# 150HzLPF_8GainPreamp.net
KiCad netlist of a schematic drawn in EAGLE
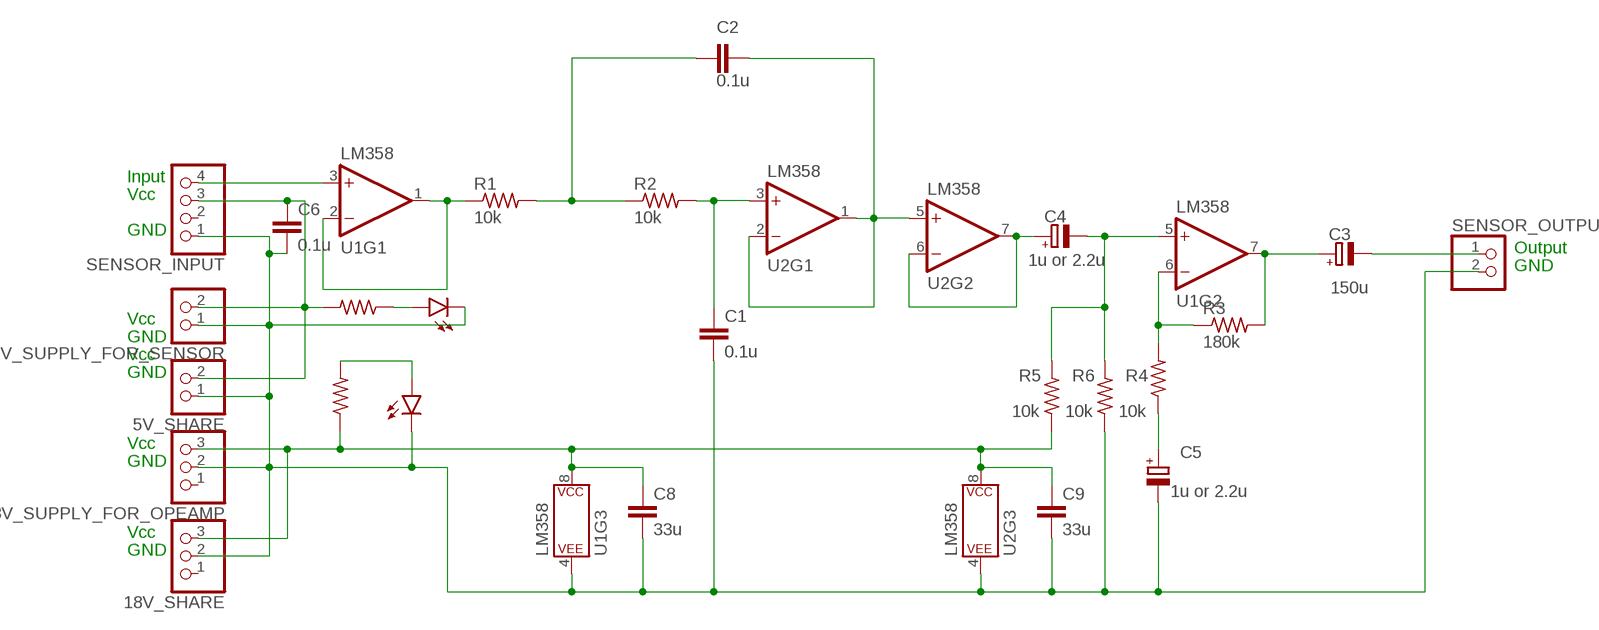
[diagram p0: schematic, sheet 1]

(export (version "E")
  (design (tool "Eeschema 10.0.6"))
  (components
    (comp (ref "5V_SHARE")
      (value "PINHD-1X2")
      (footprint "eagle-import:1X02")
      (libsource (lib "eagle-import") (part "PINHD-1X2"))
    )
    (comp (ref "5V_SUPPLY_FOR_SENSOR")
      (value "PINHD-1X2")
      (footprint "eagle-import:1X02")
      (libsource (lib "eagle-import") (part "PINHD-1X2"))
    )
    (comp (ref "18V_SHARE")
      (value "PINHD-1X3")
      (footprint "eagle-import:1X03")
      (libsource (lib "eagle-import") (part "PINHD-1X3"))
    )
    (comp (ref "18V_SUPPLY_FOR_OPEAMP")
      (value "PINHD-1X3")
      (footprint "eagle-import:1X03")
      (libsource (lib "eagle-import") (part "PINHD-1X3"))
    )
    (comp (ref "C1")
      (value "0.1u")
      (footprint "eagle-import:C050-030X075")
      (libsource (lib "eagle-import") (part "C-EU050-030X075"))
    )
    (comp (ref "C2")
      (value "0.1u")
      (footprint "eagle-import:C050-030X075")
      (libsource (lib "eagle-import") (part "C-EU050-030X075"))
    )
    (comp (ref "C3")
      (value "150u")
      (footprint "eagle-import:E5-10,5")
      (libsource (lib "eagle-import") (part "CPOL-EUE5-10.5"))
    )
    (comp (ref "C4")
      (value "1u or 2.2u")
      (footprint "eagle-import:E5-10,5")
      (libsource (lib "eagle-import") (part "CPOL-EUE5-10.5"))
    )
    (comp (ref "C5")
      (value "1u or 2.2u")
      (footprint "eagle-import:E5-10,5")
      (libsource (lib "eagle-import") (part "CPOL-EUE5-10.5"))
    )
    (comp (ref "C6")
      (value "0.1u")
      (footprint "eagle-import:C0603")
      (libsource (lib "eagle-import") (part "C-EUC0603"))
    )
    (comp (ref "C8")
      (value "33u")
      (footprint "eagle-import:C0603")
      (libsource (lib "eagle-import") (part "C-EUC0603"))
    )
    (comp (ref "C9")
      (value "33u")
      (footprint "eagle-import:C0603")
      (libsource (lib "eagle-import") (part "C-EUC0603"))
    )
    (comp (ref "D2")
      (value "LTL-1CHE")
      (footprint "eagle-import:RADIAL_3MM")
      (fields
        (field (name "DIGIKEY_PART_NUMBER") "160-1708-ND")
        (field (name "MANUFACTURER") "Lite-On Inc.")
        (field (name "CREATED_BY") "PCBLayout.com")
      )
      (libsource (lib "eagle-import") (part "LTL-1CHE"))
    )
    (comp (ref "D3")
      (value "LTL-1CHE")
      (footprint "eagle-import:RADIAL_3MM")
      (fields
        (field (name "DIGIKEY_PART_NUMBER") "160-1708-ND")
        (field (name "MANUFACTURER") "Lite-On Inc.")
        (field (name "CREATED_BY") "PCBLayout.com")
      )
      (libsource (lib "eagle-import") (part "LTL-1CHE"))
    )
    (comp (ref "R1")
      (value "10k")
      (footprint "eagle-import:0207_7")
      (libsource (lib "eagle-import") (part "R-US_0207/7"))
    )
    (comp (ref "R2")
      (value "10k")
      (footprint "eagle-import:0207_7")
      (libsource (lib "eagle-import") (part "R-US_0207/7"))
    )
    (comp (ref "R3")
      (value "180k")
      (footprint "eagle-import:0207_7")
      (libsource (lib "eagle-import") (part "R-US_0207/7"))
    )
    (comp (ref "R4")
      (value "10k")
      (footprint "eagle-import:0207_7")
      (libsource (lib "eagle-import") (part "R-US_0207/7"))
    )
    (comp (ref "R5")
      (value "10k")
      (footprint "eagle-import:0207_7")
      (libsource (lib "eagle-import") (part "R-US_0207/7"))
    )
    (comp (ref "R6")
      (value "10k")
      (footprint "eagle-import:0207_7")
      (libsource (lib "eagle-import") (part "R-US_0207/7"))
    )
    (comp (ref "R8")
      (value "760")
      (footprint "eagle-import:0207_7")
      (libsource (lib "eagle-import") (part "R-US_0207/7"))
    )
    (comp (ref "R9")
      (value "3.3k")
      (footprint "eagle-import:0207_7")
      (libsource (lib "eagle-import") (part "R-US_0207/7"))
    )
    (comp (ref "SENSOR_INPUT")
      (value "PINHD-1X4")
      (footprint "eagle-import:1X04")
      (libsource (lib "eagle-import") (part "PINHD-1X4"))
    )
    (comp (ref "SENSOR_OUTPUT")
      (value "PINHD-1X2")
      (footprint "eagle-import:1X02")
      (libsource (lib "eagle-import") (part "PINHD-1X2"))
    )
    (comp (ref "U1")
      (value "LM358")
      (footprint "eagle-import:DIP08")
      (libsource (lib "eagle-import") (part "LM358"))
    )
    (comp (ref "U2")
      (value "LM358")
      (footprint "eagle-import:DIP08")
      (libsource (lib "eagle-import") (part "LM358"))
    )
  )
  (nets
    (net (code "1") (name "Net-(5V_SHARE-Pad2)") (class "Default")
      (node (ref "5V_SHARE") (pin "2") (pinfunction "2_2") (pintype "passive"))
      (node (ref "5V_SUPPLY_FOR_SENSOR") (pin "2") (pinfunction "2_2") (pintype "passive"))
      (node (ref "C6") (pin "1") (pinfunction "1_1") (pintype "passive"))
      (node (ref "R8") (pin "2") (pinfunction "2_2") (pintype "passive"))
      (node (ref "SENSOR_INPUT") (pin "3") (pinfunction "3_3") (pintype "passive"))
    )
    (net (code "2") (name "Net-(C2-Pad2)") (class "Default")
      (node (ref "C2") (pin "2") (pinfunction "2_2") (pintype "passive"))
      (node (ref "R1") (pin "2") (pinfunction "2_2") (pintype "passive"))
      (node (ref "R2") (pin "1") (pinfunction "1_1") (pintype "passive"))
    )
    (net (code "3") (name "Net-(C3-Pad-)") (class "Default")
      (node (ref "C3") (pin "-") (pinfunction "-_-") (pintype "passive"))
      (node (ref "SENSOR_OUTPUT") (pin "1") (pinfunction "1_1") (pintype "passive"))
    )
    (net (code "4") (name "Net-(C5-Pad+)") (class "Default")
      (node (ref "C5") (pin "+") (pinfunction "+_+") (pintype "passive"))
      (node (ref "R4") (pin "1") (pinfunction "1_1") (pintype "passive"))
    )
    (net (code "5") (name "Net-(D2-PadA)") (class "Default")
      (node (ref "D2") (pin "A") (pinfunction "A_A") (pintype "passive"))
      (node (ref "R8") (pin "1") (pinfunction "1_1") (pintype "passive"))
    )
    (net (code "6") (name "Net-(D3-PadA)") (class "Default")
      (node (ref "D3") (pin "A") (pinfunction "A_A") (pintype "passive"))
      (node (ref "R9") (pin "2") (pinfunction "2_2") (pintype "passive"))
    )
    (net (code "7") (name "Net-(U1A-+IN)") (class "Default")
      (node (ref "SENSOR_INPUT") (pin "4") (pinfunction "4_4") (pintype "passive"))
      (node (ref "U1") (pin "3") (pinfunction "+IN_3") (pintype "input"))
    )
    (net (code "8") (name "Net-(U1A--IN)") (class "Default")
      (node (ref "R1") (pin "1") (pinfunction "1_1") (pintype "passive"))
      (node (ref "U1") (pin "1") (pinfunction "OUT_1") (pintype "output"))
      (node (ref "U1") (pin "2") (pinfunction "-IN_2") (pintype "input"))
    )
    (net (code "9") (name "Net-(U1B-+IN)") (class "Default")
      (node (ref "C4") (pin "-") (pinfunction "-_-") (pintype "passive"))
      (node (ref "R5") (pin "2") (pinfunction "2_2") (pintype "passive"))
      (node (ref "R6") (pin "2") (pinfunction "2_2") (pintype "passive"))
      (node (ref "U1") (pin "5") (pinfunction "+IN_5") (pintype "input"))
    )
    (net (code "10") (name "Net-(U1B--IN)") (class "Default")
      (node (ref "R3") (pin "1") (pinfunction "1_1") (pintype "passive"))
      (node (ref "R4") (pin "2") (pinfunction "2_2") (pintype "passive"))
      (node (ref "U1") (pin "6") (pinfunction "-IN_6") (pintype "input"))
    )
    (net (code "11") (name "Net-(U1B-OUT)") (class "Default")
      (node (ref "C3") (pin "+") (pinfunction "+_+") (pintype "passive"))
      (node (ref "R3") (pin "2") (pinfunction "2_2") (pintype "passive"))
      (node (ref "U1") (pin "7") (pinfunction "OUT_7") (pintype "output"))
    )
    (net (code "12") (name "Net-(U1C-P$V+)") (class "Default")
      (node (ref "18V_SHARE") (pin "3") (pinfunction "3_3") (pintype "passive"))
      (node (ref "18V_SUPPLY_FOR_OPEAMP") (pin "3") (pinfunction "3_3") (pintype "passive"))
      (node (ref "C8") (pin "1") (pinfunction "1_1") (pintype "passive"))
      (node (ref "C9") (pin "1") (pinfunction "1_1") (pintype "passive"))
      (node (ref "R5") (pin "1") (pinfunction "1_1") (pintype "passive"))
      (node (ref "R9") (pin "1") (pinfunction "1_1") (pintype "passive"))
      (node (ref "U1") (pin "8") (pinfunction "P$V+_8") (pintype "bidirectional"))
      (node (ref "U2") (pin "8") (pinfunction "P$V+_8") (pintype "bidirectional"))
    )
    (net (code "13") (name "Net-(U1C-P$V-)") (class "Default")
      (node (ref "18V_SHARE") (pin "2") (pinfunction "2_2") (pintype "passive"))
      (node (ref "18V_SUPPLY_FOR_OPEAMP") (pin "2") (pinfunction "2_2") (pintype "passive"))
      (node (ref "5V_SHARE") (pin "1") (pinfunction "1_1") (pintype "passive"))
      (node (ref "5V_SUPPLY_FOR_SENSOR") (pin "1") (pinfunction "1_1") (pintype "passive"))
      (node (ref "C1") (pin "2") (pinfunction "2_2") (pintype "passive"))
      (node (ref "C5") (pin "-") (pinfunction "-_-") (pintype "passive"))
      (node (ref "C6") (pin "2") (pinfunction "2_2") (pintype "passive"))
      (node (ref "C8") (pin "2") (pinfunction "2_2") (pintype "passive"))
      (node (ref "C9") (pin "2") (pinfunction "2_2") (pintype "passive"))
      (node (ref "D2") (pin "C") (pinfunction "C_C") (pintype "passive"))
      (node (ref "D3") (pin "C") (pinfunction "C_C") (pintype "passive"))
      (node (ref "R6") (pin "1") (pinfunction "1_1") (pintype "passive"))
      (node (ref "SENSOR_INPUT") (pin "1") (pinfunction "1_1") (pintype "passive"))
      (node (ref "SENSOR_OUTPUT") (pin "2") (pinfunction "2_2") (pintype "passive"))
      (node (ref "U1") (pin "4") (pinfunction "P$V-_4") (pintype "bidirectional"))
      (node (ref "U2") (pin "4") (pinfunction "P$V-_4") (pintype "bidirectional"))
    )
    (net (code "14") (name "Net-(U2A-+IN)") (class "Default")
      (node (ref "C1") (pin "1") (pinfunction "1_1") (pintype "passive"))
      (node (ref "R2") (pin "2") (pinfunction "2_2") (pintype "passive"))
      (node (ref "U2") (pin "3") (pinfunction "+IN_3") (pintype "input"))
    )
    (net (code "15") (name "Net-(U2A--IN)") (class "Default")
      (node (ref "C2") (pin "1") (pinfunction "1_1") (pintype "passive"))
      (node (ref "U2") (pin "1") (pinfunction "OUT_1") (pintype "output"))
      (node (ref "U2") (pin "2") (pinfunction "-IN_2") (pintype "input"))
      (node (ref "U2") (pin "5") (pinfunction "+IN_5") (pintype "input"))
    )
    (net (code "16") (name "Net-(U2B--IN)") (class "Default")
      (node (ref "C4") (pin "+") (pinfunction "+_+") (pintype "passive"))
      (node (ref "U2") (pin "6") (pinfunction "-IN_6") (pintype "input"))
      (node (ref "U2") (pin "7") (pinfunction "OUT_7") (pintype "output"))
    )
    (net (code "17") (name "unconnected-(18V_SHARE-Pad1)") (class "Default")
      (node (ref "18V_SHARE") (pin "1") (pinfunction "1_1") (pintype "passive"))
    )
    (net (code "18") (name "unconnected-(18V_SUPPLY_FOR_OPEAMP-Pad1)") (class "Default")
      (node (ref "18V_SUPPLY_FOR_OPEAMP") (pin "1") (pinfunction "1_1") (pintype "passive"))
    )
    (net (code "19") (name "unconnected-(SENSOR_INPUT-Pad2)") (class "Default")
      (node (ref "SENSOR_INPUT") (pin "2") (pinfunction "2_2") (pintype "passive"))
    )
  )
)
